# relay_pulvertech_lite.net
KiCad netlist of a schematic drawn in EAGLE
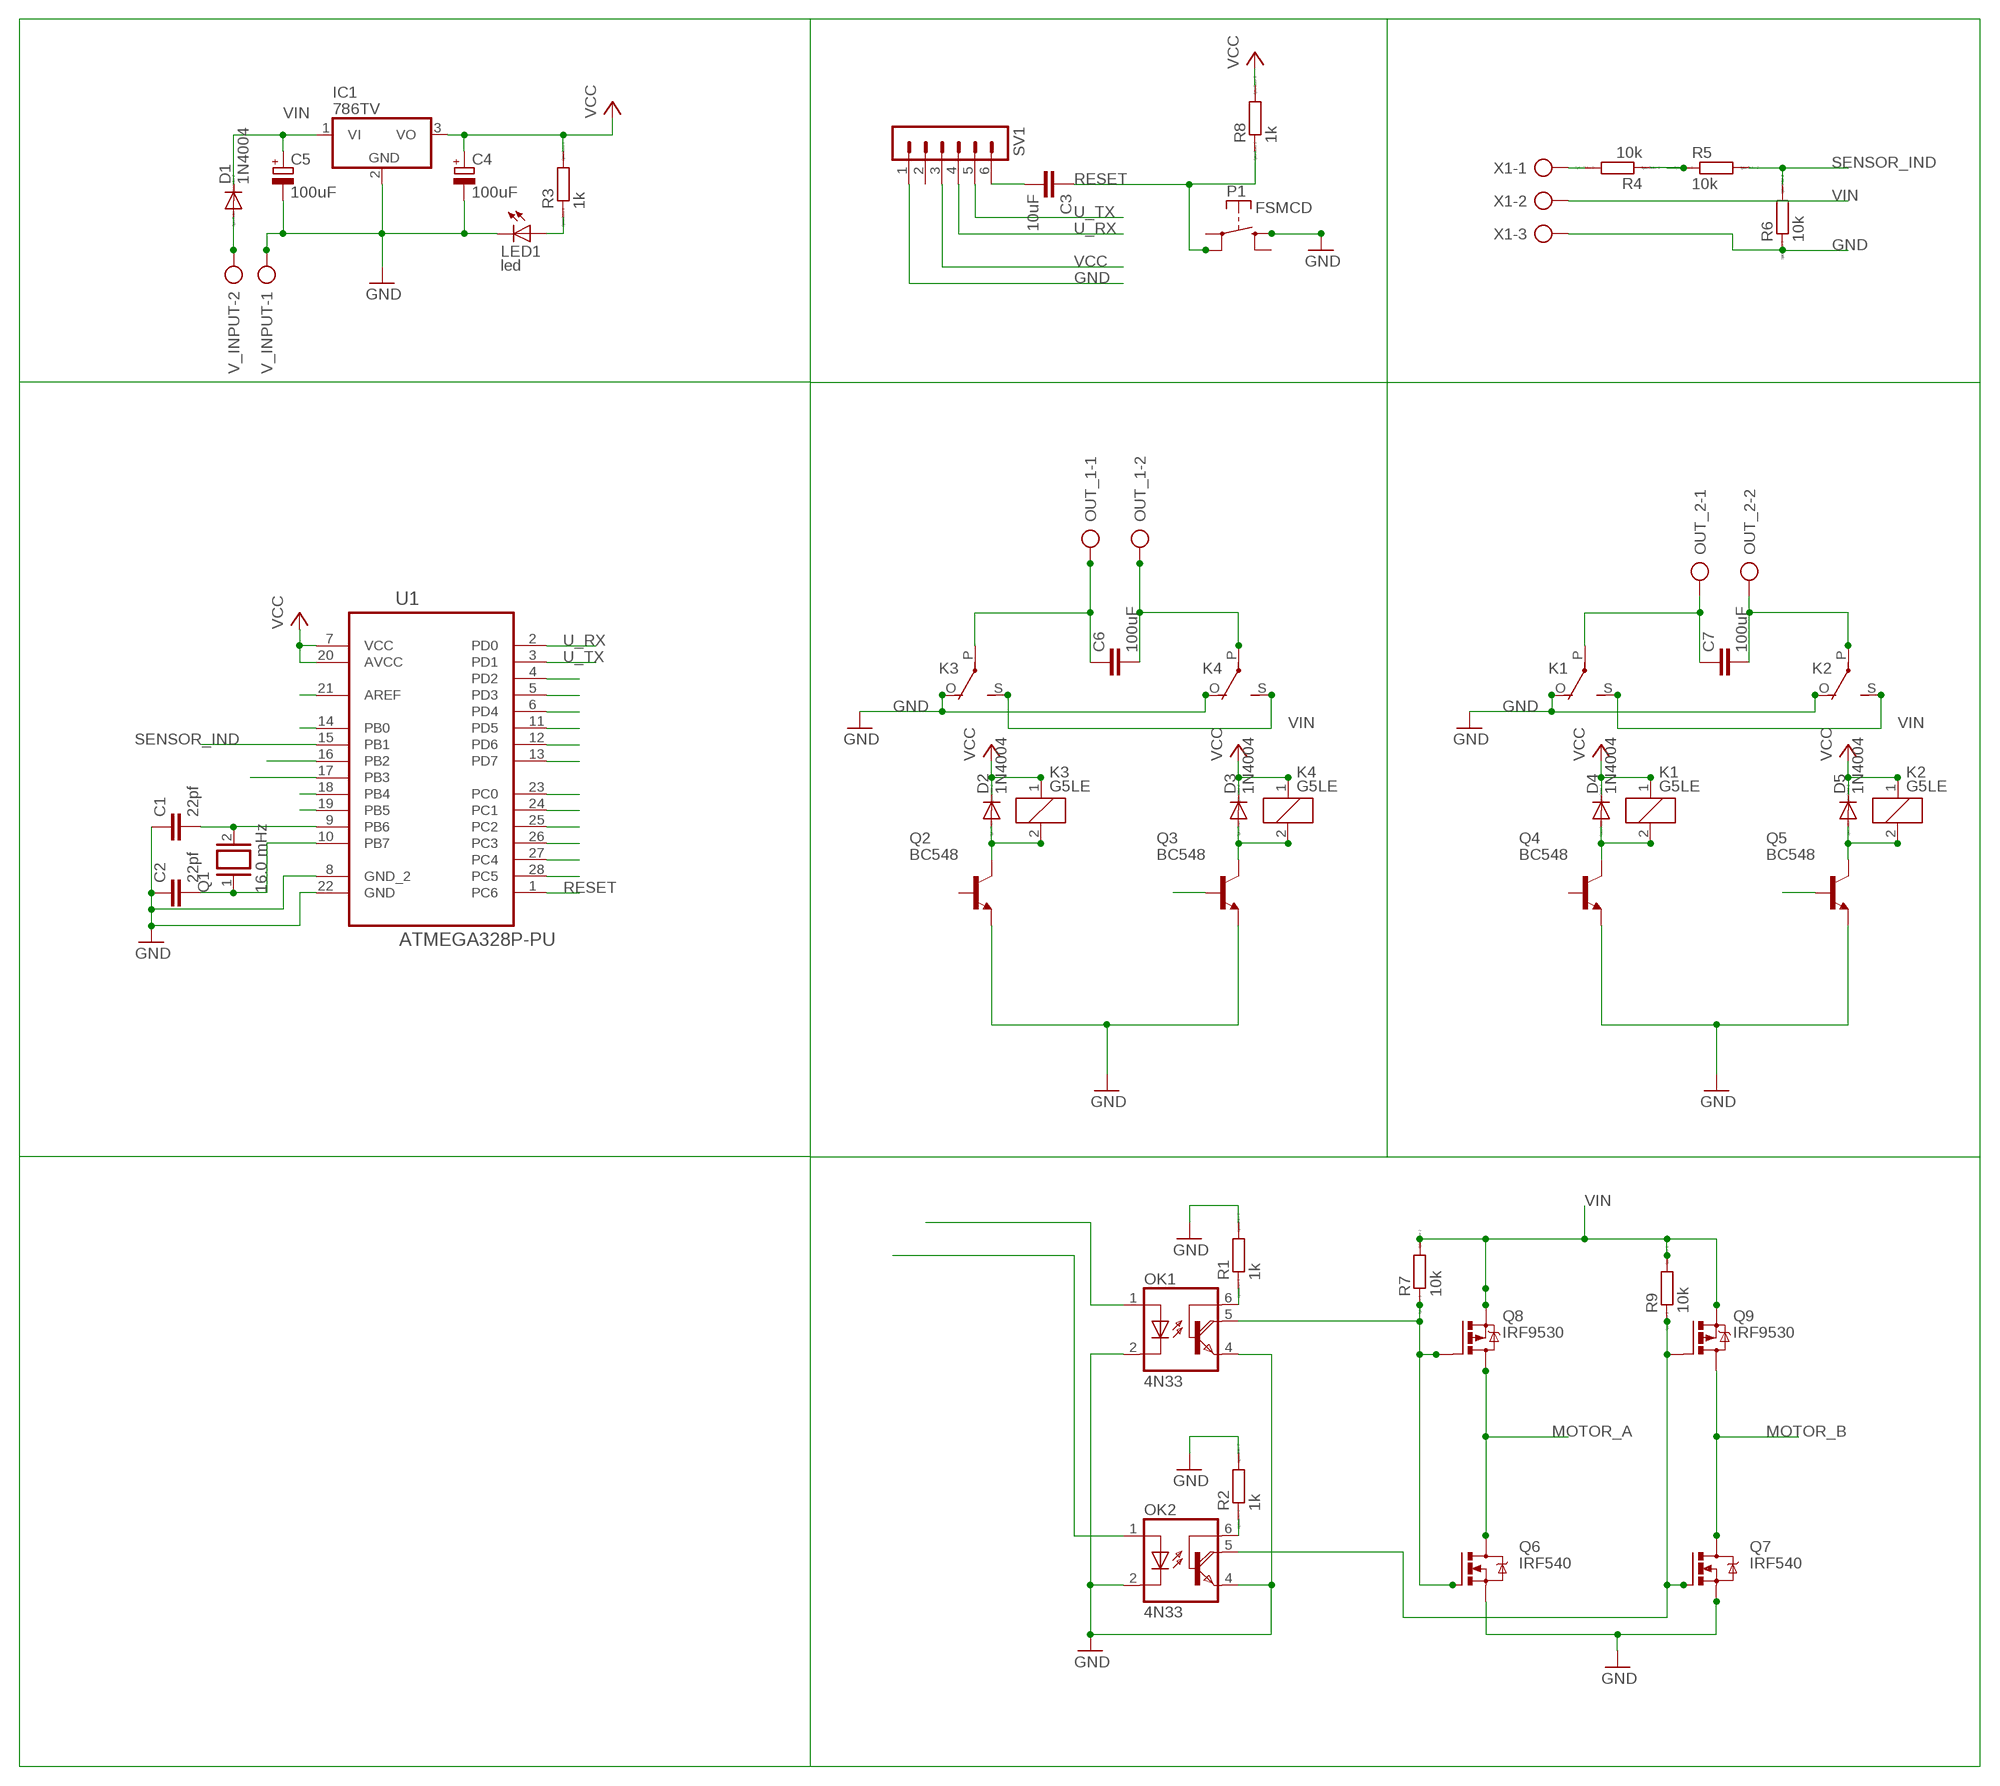
[diagram p0: schematic, sheet 1]

(export (version "E")
  (design (tool "Eeschema 10.0.6"))
  (components
    (comp (ref "C1")
      (value "22pf")
      (footprint "eagle-import:C025-025X050")
      (libsource (lib "eagle-import") (part "C-EU025-025X050"))
    )
    (comp (ref "C2")
      (value "22pf")
      (footprint "eagle-import:C025-025X050")
      (libsource (lib "eagle-import") (part "C-EU025-025X050"))
    )
    (comp (ref "C3")
      (value "10uF")
      (footprint "eagle-import:C025-025X050")
      (libsource (lib "eagle-import") (part "C-EU025-025X050"))
    )
    (comp (ref "C4")
      (value "100uF")
      (footprint "eagle-import:E2,5-5")
      (libsource (lib "eagle-import") (part "CPOL-EUE2.5-5"))
    )
    (comp (ref "C5")
      (value "100uF")
      (footprint "eagle-import:E2,5-5")
      (libsource (lib "eagle-import") (part "CPOL-EUE2.5-5"))
    )
    (comp (ref "C6")
      (value "100uF")
      (footprint "eagle-import:C2.5-3")
      (libsource (lib "eagle-import") (part "C2,5-3"))
    )
    (comp (ref "C7")
      (value "100uF")
      (footprint "eagle-import:C2.5-3")
      (libsource (lib "eagle-import") (part "C2,5-3"))
    )
    (comp (ref "D1")
      (value "1N4004")
      (footprint "eagle-import:DO41-10")
      (libsource (lib "eagle-import") (part "1N4004"))
    )
    (comp (ref "D2")
      (value "1N4004")
      (footprint "eagle-import:DO41-10")
      (libsource (lib "eagle-import") (part "1N4004"))
    )
    (comp (ref "D3")
      (value "1N4004")
      (footprint "eagle-import:DO41-10")
      (libsource (lib "eagle-import") (part "1N4004"))
    )
    (comp (ref "D4")
      (value "1N4004")
      (footprint "eagle-import:DO41-10")
      (libsource (lib "eagle-import") (part "1N4004"))
    )
    (comp (ref "D5")
      (value "1N4004")
      (footprint "eagle-import:DO41-10")
      (libsource (lib "eagle-import") (part "1N4004"))
    )
    (comp (ref "IC1")
      (value "786TV")
      (footprint "eagle-import:TO220V")
      (libsource (lib "eagle-import") (part "78TV6"))
    )
    (comp (ref "K1")
      (value "G5LE")
      (footprint "eagle-import:G5LE")
      (libsource (lib "eagle-import") (part "G5LE"))
    )
    (comp (ref "K2")
      (value "G5LE")
      (footprint "eagle-import:G5LE")
      (libsource (lib "eagle-import") (part "G5LE"))
    )
    (comp (ref "K3")
      (value "G5LE")
      (footprint "eagle-import:G5LE")
      (libsource (lib "eagle-import") (part "G5LE"))
    )
    (comp (ref "K4")
      (value "G5LE")
      (footprint "eagle-import:G5LE")
      (libsource (lib "eagle-import") (part "G5LE"))
    )
    (comp (ref "LED1")
      (value "led")
      (footprint "eagle-import:LED3MM")
      (libsource (lib "eagle-import") (part "LED3MM"))
    )
    (comp (ref "OK1")
      (value "4N33")
      (footprint "eagle-import:DIL06")
      (fields (field (name "MF") "VISHAY/TELEFUNKEN"))
      (libsource (lib "eagle-import") (part "4N33"))
    )
    (comp (ref "OK2")
      (value "4N33")
      (footprint "eagle-import:DIL06")
      (fields (field (name "MF") "VISHAY/TELEFUNKEN"))
      (libsource (lib "eagle-import") (part "4N33"))
    )
    (comp (ref "OUT_1")
      (value "AK500/2-H")
      (footprint "eagle-import:AK500_2-H")
      (libsource (lib "eagle-import") (part "AK500/2-H"))
    )
    (comp (ref "OUT_2")
      (value "AK500/2-H")
      (footprint "eagle-import:AK500_2-H")
      (libsource (lib "eagle-import") (part "AK500/2-H"))
    )
    (comp (ref "P1")
      (value "FSMCD")
      (footprint "eagle-import:FSMCD")
      (libsource (lib "eagle-import") (part "FSMCD"))
    )
    (comp (ref "Q1")
      (value "16.0 mHz")
      (footprint "eagle-import:QS")
      (libsource (lib "eagle-import") (part "XTAL/S"))
    )
    (comp (ref "Q2")
      (value "BC548")
      (footprint "eagle-import:TO92-EBC")
      (libsource (lib "eagle-import") (part "BC548"))
    )
    (comp (ref "Q3")
      (value "BC548")
      (footprint "eagle-import:TO92-EBC")
      (libsource (lib "eagle-import") (part "BC548"))
    )
    (comp (ref "Q4")
      (value "BC548")
      (footprint "eagle-import:TO92-EBC")
      (libsource (lib "eagle-import") (part "BC548"))
    )
    (comp (ref "Q5")
      (value "BC548")
      (footprint "eagle-import:TO92-EBC")
      (libsource (lib "eagle-import") (part "BC548"))
    )
    (comp (ref "Q6")
      (value "IRF540")
      (footprint "eagle-import:TO220BV")
      (libsource (lib "eagle-import") (part "IRF540"))
    )
    (comp (ref "Q7")
      (value "IRF540")
      (footprint "eagle-import:TO220BV")
      (libsource (lib "eagle-import") (part "IRF540"))
    )
    (comp (ref "Q8")
      (value "IRF9530")
      (footprint "eagle-import:TO220BV")
      (libsource (lib "eagle-import") (part "IRF9530"))
    )
    (comp (ref "Q9")
      (value "IRF9530")
      (footprint "eagle-import:TO220BV")
      (libsource (lib "eagle-import") (part "IRF9530"))
    )
    (comp (ref "R1")
      (value "1k")
      (footprint "eagle-import:0204_7")
      (libsource (lib "eagle-import") (part "R0204/7"))
    )
    (comp (ref "R2")
      (value "1k")
      (footprint "eagle-import:0204_7")
      (libsource (lib "eagle-import") (part "R0204/7"))
    )
    (comp (ref "R3")
      (value "1k")
      (footprint "eagle-import:0204_7")
      (libsource (lib "eagle-import") (part "R0204/7"))
    )
    (comp (ref "R4")
      (value "10k")
      (footprint "eagle-import:0204_7")
      (libsource (lib "eagle-import") (part "R0204/7"))
    )
    (comp (ref "R5")
      (value "10k")
      (footprint "eagle-import:0204_7")
      (libsource (lib "eagle-import") (part "R0204/7"))
    )
    (comp (ref "R6")
      (value "10k")
      (footprint "eagle-import:0204_7")
      (libsource (lib "eagle-import") (part "R0204/7"))
    )
    (comp (ref "R7")
      (value "10k")
      (footprint "eagle-import:0204_7")
      (libsource (lib "eagle-import") (part "R0204/7"))
    )
    (comp (ref "R8")
      (value "1k")
      (footprint "eagle-import:0204_7")
      (libsource (lib "eagle-import") (part "R0204/7"))
    )
    (comp (ref "R9")
      (value "10k")
      (footprint "eagle-import:0204_7")
      (libsource (lib "eagle-import") (part "R0204/7"))
    )
    (comp (ref "SV1")
      (value "MA06-1")
      (footprint "eagle-import:MA06-1")
      (libsource (lib "eagle-import") (part "MA06-1"))
    )
    (comp (ref "U1")
      (value "ATMEGA328P-PU")
      (footprint "eagle-import:DIP254P762X457-28")
      (libsource (lib "eagle-import") (part "ATMEGA328P-PU"))
    )
    (comp (ref "V_INPUT")
      (value "AK500/2-H")
      (footprint "eagle-import:AK500_2-H")
      (libsource (lib "eagle-import") (part "AK500/2-H"))
    )
    (comp (ref "X1")
      (value "AK500/3-H")
      (footprint "eagle-import:AK500_3-H")
      (libsource (lib "eagle-import") (part "AK500/3-H"))
    )
  )
  (nets
    (net (code "1") (name "/MOTOR_A") (class "Default")
      (node (ref "Q6") (pin "D") (pinfunction "D_D") (pintype "passive"))
      (node (ref "Q8") (pin "D") (pinfunction "D_D") (pintype "passive"))
    )
    (net (code "2") (name "/MOTOR_B") (class "Default")
      (node (ref "Q7") (pin "D") (pinfunction "D_D") (pintype "passive"))
      (node (ref "Q9") (pin "D") (pinfunction "D_D") (pintype "passive"))
    )
    (net (code "3") (name "/RESET") (class "Default")
      (node (ref "C3") (pin "1") (pinfunction "1_1") (pintype "passive"))
      (node (ref "P1") (pin "P$2") (pinfunction "P_P$2") (pintype "passive"))
      (node (ref "R8") (pin "1") (pinfunction "1_1") (pintype "passive"))
      (node (ref "U1") (pin "1") (pinfunction "PC6_1") (pintype "bidirectional"))
    )
    (net (code "4") (name "/SENSOR_IND") (class "Default")
      (node (ref "R5") (pin "2") (pinfunction "2_2") (pintype "passive"))
      (node (ref "R6") (pin "2") (pinfunction "2_2") (pintype "passive"))
      (node (ref "U1") (pin "15") (pinfunction "PB1_15") (pintype "bidirectional"))
    )
    (net (code "5") (name "/U_RX") (class "Default")
      (node (ref "SV1") (pin "4") (pinfunction "4_4") (pintype "passive"))
      (node (ref "U1") (pin "2") (pinfunction "PD0_2") (pintype "bidirectional"))
    )
    (net (code "6") (name "/U_TX") (class "Default")
      (node (ref "SV1") (pin "5") (pinfunction "5_5") (pintype "passive"))
      (node (ref "U1") (pin "3") (pinfunction "PD1_3") (pintype "bidirectional"))
    )
    (net (code "7") (name "/VIN") (class "Default")
      (node (ref "C5") (pin "+") (pinfunction "+_+") (pintype "passive"))
      (node (ref "D1") (pin "C") (pinfunction "C_C") (pintype "passive"))
      (node (ref "IC1") (pin "1") (pinfunction "VI_1") (pintype "input"))
      (node (ref "K1") (pin "S") (pinfunction "S_S") (pintype "passive"))
      (node (ref "K2") (pin "S") (pinfunction "S_S") (pintype "passive"))
      (node (ref "K3") (pin "S") (pinfunction "S_S") (pintype "passive"))
      (node (ref "K4") (pin "S") (pinfunction "S_S") (pintype "passive"))
      (node (ref "Q8") (pin "S") (pinfunction "S_S") (pintype "passive"))
      (node (ref "Q9") (pin "S") (pinfunction "S_S") (pintype "passive"))
      (node (ref "R7") (pin "2") (pinfunction "2_2") (pintype "passive"))
      (node (ref "R9") (pin "2") (pinfunction "2_2") (pintype "passive"))
      (node (ref "X1") (pin "2") (pinfunction "KL_2") (pintype "passive"))
    )
    (net (code "8") (name "GND") (class "Default")
      (node (ref "C1") (pin "1") (pinfunction "1_1") (pintype "passive"))
      (node (ref "C2") (pin "1") (pinfunction "1_1") (pintype "passive"))
      (node (ref "C4") (pin "-") (pinfunction "-_-") (pintype "passive"))
      (node (ref "C5") (pin "-") (pinfunction "-_-") (pintype "passive"))
      (node (ref "IC1") (pin "2") (pinfunction "GND_2") (pintype "passive"))
      (node (ref "K1") (pin "O") (pinfunction "O_O") (pintype "passive"))
      (node (ref "K2") (pin "O") (pinfunction "O_O") (pintype "passive"))
      (node (ref "K3") (pin "O") (pinfunction "O_O") (pintype "passive"))
      (node (ref "K4") (pin "O") (pinfunction "O_O") (pintype "passive"))
      (node (ref "LED1") (pin "K") (pinfunction "C_K") (pintype "passive"))
      (node (ref "OK1") (pin "2") (pinfunction "C_2") (pintype "passive"))
      (node (ref "OK1") (pin "4") (pinfunction "E_4") (pintype "passive"))
      (node (ref "OK2") (pin "2") (pinfunction "C_2") (pintype "passive"))
      (node (ref "OK2") (pin "4") (pinfunction "E_4") (pintype "passive"))
      (node (ref "P1") (pin "P$3") (pinfunction "S_P$3") (pintype "passive"))
      (node (ref "Q2") (pin "E") (pinfunction "E_E") (pintype "passive"))
      (node (ref "Q3") (pin "E") (pinfunction "E_E") (pintype "passive"))
      (node (ref "Q4") (pin "E") (pinfunction "E_E") (pintype "passive"))
      (node (ref "Q5") (pin "E") (pinfunction "E_E") (pintype "passive"))
      (node (ref "Q6") (pin "S") (pinfunction "S_S") (pintype "passive"))
      (node (ref "Q7") (pin "S") (pinfunction "S_S") (pintype "passive"))
      (node (ref "R1") (pin "2") (pinfunction "2_2") (pintype "passive"))
      (node (ref "R2") (pin "2") (pinfunction "2_2") (pintype "passive"))
      (node (ref "R6") (pin "1") (pinfunction "1_1") (pintype "passive"))
      (node (ref "SV1") (pin "1") (pinfunction "1_1") (pintype "passive"))
      (node (ref "U1") (pin "22") (pinfunction "GND_22") (pintype "passive"))
      (node (ref "U1") (pin "8") (pinfunction "GND_2_8") (pintype "passive"))
      (node (ref "V_INPUT") (pin "1") (pinfunction "KL_1") (pintype "passive"))
      (node (ref "X1") (pin "3") (pinfunction "KL_3") (pintype "passive"))
    )
    (net (code "9") (name "Net-(C3-Pad2)") (class "Default")
      (node (ref "C3") (pin "2") (pinfunction "2_2") (pintype "passive"))
      (node (ref "SV1") (pin "6") (pinfunction "6_6") (pintype "passive"))
    )
    (net (code "10") (name "Net-(D2-PadA)") (class "Default")
      (node (ref "D2") (pin "A") (pinfunction "A_A") (pintype "passive"))
      (node (ref "K3") (pin "2") (pinfunction "2_2") (pintype "passive"))
      (node (ref "Q2") (pin "C") (pinfunction "C_C") (pintype "passive"))
    )
    (net (code "11") (name "Net-(D3-PadA)") (class "Default")
      (node (ref "D3") (pin "A") (pinfunction "A_A") (pintype "passive"))
      (node (ref "K4") (pin "2") (pinfunction "2_2") (pintype "passive"))
      (node (ref "Q3") (pin "C") (pinfunction "C_C") (pintype "passive"))
    )
    (net (code "12") (name "Net-(D4-PadA)") (class "Default")
      (node (ref "D4") (pin "A") (pinfunction "A_A") (pintype "passive"))
      (node (ref "K1") (pin "2") (pinfunction "2_2") (pintype "passive"))
      (node (ref "Q4") (pin "C") (pinfunction "C_C") (pintype "passive"))
    )
    (net (code "13") (name "Net-(D5-PadA)") (class "Default")
      (node (ref "D5") (pin "A") (pinfunction "A_A") (pintype "passive"))
      (node (ref "K2") (pin "2") (pinfunction "2_2") (pintype "passive"))
      (node (ref "Q5") (pin "C") (pinfunction "C_C") (pintype "passive"))
    )
    (net (code "14") (name "Net-(LED1-PadA)") (class "Default")
      (node (ref "LED1") (pin "A") (pinfunction "A_A") (pintype "passive"))
      (node (ref "R3") (pin "1") (pinfunction "1_1") (pintype "passive"))
    )
    (net (code "15") (name "Net-(OK1-B)") (class "Default")
      (node (ref "OK1") (pin "6") (pinfunction "B_6") (pintype "passive"))
      (node (ref "R1") (pin "1") (pinfunction "1_1") (pintype "passive"))
    )
    (net (code "16") (name "Net-(OK1-COL)") (class "Default")
      (node (ref "OK1") (pin "5") (pinfunction "COL_5") (pintype "passive"))
      (node (ref "Q6") (pin "G") (pinfunction "G_G") (pintype "passive"))
      (node (ref "Q8") (pin "G") (pinfunction "G_G") (pintype "passive"))
      (node (ref "R7") (pin "1") (pinfunction "1_1") (pintype "passive"))
    )
    (net (code "17") (name "Net-(OK2-B)") (class "Default")
      (node (ref "OK2") (pin "6") (pinfunction "B_6") (pintype "passive"))
      (node (ref "R2") (pin "1") (pinfunction "1_1") (pintype "passive"))
    )
    (net (code "18") (name "Net-(OK2-COL)") (class "Default")
      (node (ref "OK2") (pin "5") (pinfunction "COL_5") (pintype "passive"))
      (node (ref "Q7") (pin "G") (pinfunction "G_G") (pintype "passive"))
      (node (ref "Q9") (pin "G") (pinfunction "G_G") (pintype "passive"))
      (node (ref "R9") (pin "1") (pinfunction "1_1") (pintype "passive"))
    )
    (net (code "19") (name "Net-(OUT_1A-KL)") (class "Default")
      (node (ref "C6") (pin "1") (pinfunction "1_1") (pintype "passive"))
      (node (ref "K3") (pin "P") (pinfunction "P_P") (pintype "passive"))
      (node (ref "OUT_1") (pin "1") (pinfunction "KL_1") (pintype "passive"))
    )
    (net (code "20") (name "Net-(OUT_1B-KL)") (class "Default")
      (node (ref "C6") (pin "2") (pinfunction "2_2") (pintype "passive"))
      (node (ref "K4") (pin "P") (pinfunction "P_P") (pintype "passive"))
      (node (ref "OUT_1") (pin "2") (pinfunction "KL_2") (pintype "passive"))
    )
    (net (code "21") (name "Net-(OUT_2A-KL)") (class "Default")
      (node (ref "C7") (pin "1") (pinfunction "1_1") (pintype "passive"))
      (node (ref "K1") (pin "P") (pinfunction "P_P") (pintype "passive"))
      (node (ref "OUT_2") (pin "1") (pinfunction "KL_1") (pintype "passive"))
    )
    (net (code "22") (name "Net-(OUT_2B-KL)") (class "Default")
      (node (ref "C7") (pin "2") (pinfunction "2_2") (pintype "passive"))
      (node (ref "K2") (pin "P") (pinfunction "P_P") (pintype "passive"))
      (node (ref "OUT_2") (pin "2") (pinfunction "KL_2") (pintype "passive"))
    )
    (net (code "23") (name "Net-(R4-Pad1)") (class "Default")
      (node (ref "R4") (pin "1") (pinfunction "1_1") (pintype "passive"))
      (node (ref "R5") (pin "1") (pinfunction "1_1") (pintype "passive"))
    )
    (net (code "24") (name "Net-(U1-PB6)") (class "Default")
      (node (ref "C1") (pin "2") (pinfunction "2_2") (pintype "passive"))
      (node (ref "Q1") (pin "2") (pinfunction "2_2") (pintype "passive"))
      (node (ref "U1") (pin "9") (pinfunction "PB6_9") (pintype "bidirectional"))
    )
    (net (code "25") (name "Net-(U1-PB7)") (class "Default")
      (node (ref "C2") (pin "2") (pinfunction "2_2") (pintype "passive"))
      (node (ref "Q1") (pin "1") (pinfunction "1_1") (pintype "passive"))
      (node (ref "U1") (pin "10") (pinfunction "PB7_10") (pintype "bidirectional"))
    )
    (net (code "26") (name "Net-(V_INPUTB-KL)") (class "Default")
      (node (ref "D1") (pin "A") (pinfunction "A_A") (pintype "passive"))
      (node (ref "V_INPUT") (pin "2") (pinfunction "KL_2") (pintype "passive"))
    )
    (net (code "27") (name "Net-(X1A-KL)") (class "Default")
      (node (ref "R4") (pin "2") (pinfunction "2_2") (pintype "passive"))
      (node (ref "X1") (pin "1") (pinfunction "KL_1") (pintype "passive"))
    )
    (net (code "28") (name "VCC") (class "Default")
      (node (ref "C4") (pin "+") (pinfunction "+_+") (pintype "passive"))
      (node (ref "D2") (pin "C") (pinfunction "C_C") (pintype "passive"))
      (node (ref "D3") (pin "C") (pinfunction "C_C") (pintype "passive"))
      (node (ref "D4") (pin "C") (pinfunction "C_C") (pintype "passive"))
      (node (ref "D5") (pin "C") (pinfunction "C_C") (pintype "passive"))
      (node (ref "IC1") (pin "3") (pinfunction "VO_3") (pintype "passive"))
      (node (ref "K1") (pin "1") (pinfunction "1_1") (pintype "passive"))
      (node (ref "K2") (pin "1") (pinfunction "1_1") (pintype "passive"))
      (node (ref "K3") (pin "1") (pinfunction "1_1") (pintype "passive"))
      (node (ref "K4") (pin "1") (pinfunction "1_1") (pintype "passive"))
      (node (ref "R3") (pin "2") (pinfunction "2_2") (pintype "passive"))
      (node (ref "R8") (pin "2") (pinfunction "2_2") (pintype "passive"))
      (node (ref "SV1") (pin "3") (pinfunction "3_3") (pintype "passive"))
      (node (ref "U1") (pin "20") (pinfunction "AVCC_20") (pintype "power_in"))
      (node (ref "U1") (pin "7") (pinfunction "VCC_7") (pintype "power_in"))
    )
    (net (code "29") (name "unconnected-(OK1-A-Pad1)") (class "Default")
      (node (ref "OK1") (pin "1") (pinfunction "A_1") (pintype "passive"))
    )
    (net (code "30") (name "unconnected-(OK2-A-Pad1)") (class "Default")
      (node (ref "OK2") (pin "1") (pinfunction "A_1") (pintype "passive"))
    )
    (net (code "31") (name "unconnected-(P1-P-PadP$1)") (class "Default")
      (node (ref "P1") (pin "P$1") (pinfunction "P_P$1") (pintype "passive"))
    )
    (net (code "32") (name "unconnected-(P1-S-PadP$4)") (class "Default")
      (node (ref "P1") (pin "P$4") (pinfunction "S_P$4") (pintype "passive"))
    )
    (net (code "33") (name "unconnected-(Q2-PadB)") (class "Default")
      (node (ref "Q2") (pin "B") (pinfunction "B_B") (pintype "passive"))
    )
    (net (code "34") (name "unconnected-(Q3-PadB)") (class "Default")
      (node (ref "Q3") (pin "B") (pinfunction "B_B") (pintype "passive"))
    )
    (net (code "35") (name "unconnected-(Q4-PadB)") (class "Default")
      (node (ref "Q4") (pin "B") (pinfunction "B_B") (pintype "passive"))
    )
    (net (code "36") (name "unconnected-(Q5-PadB)") (class "Default")
      (node (ref "Q5") (pin "B") (pinfunction "B_B") (pintype "passive"))
    )
    (net (code "37") (name "unconnected-(SV1-Pad2)") (class "Default")
      (node (ref "SV1") (pin "2") (pinfunction "2_2") (pintype "passive"))
    )
    (net (code "38") (name "unconnected-(U1-AREF-Pad21)") (class "Default")
      (node (ref "U1") (pin "21") (pinfunction "AREF_21") (pintype "input"))
    )
    (net (code "39") (name "unconnected-(U1-PB0-Pad14)") (class "Default")
      (node (ref "U1") (pin "14") (pinfunction "PB0_14") (pintype "bidirectional"))
    )
    (net (code "40") (name "unconnected-(U1-PB2-Pad16)") (class "Default")
      (node (ref "U1") (pin "16") (pinfunction "PB2_16") (pintype "bidirectional"))
    )
    (net (code "41") (name "unconnected-(U1-PB3-Pad17)") (class "Default")
      (node (ref "U1") (pin "17") (pinfunction "PB3_17") (pintype "bidirectional"))
    )
    (net (code "42") (name "unconnected-(U1-PB4-Pad18)") (class "Default")
      (node (ref "U1") (pin "18") (pinfunction "PB4_18") (pintype "bidirectional"))
    )
    (net (code "43") (name "unconnected-(U1-PB5-Pad19)") (class "Default")
      (node (ref "U1") (pin "19") (pinfunction "PB5_19") (pintype "bidirectional"))
    )
    (net (code "44") (name "unconnected-(U1-PC0-Pad23)") (class "Default")
      (node (ref "U1") (pin "23") (pinfunction "PC0_23") (pintype "bidirectional"))
    )
    (net (code "45") (name "unconnected-(U1-PC1-Pad24)") (class "Default")
      (node (ref "U1") (pin "24") (pinfunction "PC1_24") (pintype "bidirectional"))
    )
    (net (code "46") (name "unconnected-(U1-PC2-Pad25)") (class "Default")
      (node (ref "U1") (pin "25") (pinfunction "PC2_25") (pintype "bidirectional"))
    )
    (net (code "47") (name "unconnected-(U1-PC3-Pad26)") (class "Default")
      (node (ref "U1") (pin "26") (pinfunction "PC3_26") (pintype "bidirectional"))
    )
    (net (code "48") (name "unconnected-(U1-PC4-Pad27)") (class "Default")
      (node (ref "U1") (pin "27") (pinfunction "PC4_27") (pintype "bidirectional"))
    )
    (net (code "49") (name "unconnected-(U1-PC5-Pad28)") (class "Default")
      (node (ref "U1") (pin "28") (pinfunction "PC5_28") (pintype "bidirectional"))
    )
    (net (code "50") (name "unconnected-(U1-PD2-Pad4)") (class "Default")
      (node (ref "U1") (pin "4") (pinfunction "PD2_4") (pintype "bidirectional"))
    )
    (net (code "51") (name "unconnected-(U1-PD3-Pad5)") (class "Default")
      (node (ref "U1") (pin "5") (pinfunction "PD3_5") (pintype "bidirectional"))
    )
    (net (code "52") (name "unconnected-(U1-PD4-Pad6)") (class "Default")
      (node (ref "U1") (pin "6") (pinfunction "PD4_6") (pintype "bidirectional"))
    )
    (net (code "53") (name "unconnected-(U1-PD5-Pad11)") (class "Default")
      (node (ref "U1") (pin "11") (pinfunction "PD5_11") (pintype "bidirectional"))
    )
    (net (code "54") (name "unconnected-(U1-PD6-Pad12)") (class "Default")
      (node (ref "U1") (pin "12") (pinfunction "PD6_12") (pintype "bidirectional"))
    )
    (net (code "55") (name "unconnected-(U1-PD7-Pad13)") (class "Default")
      (node (ref "U1") (pin "13") (pinfunction "PD7_13") (pintype "bidirectional"))
    )
  )
)
